# IQRB-1_Evo_board.net
KiCad netlist of a schematic drawn in EAGLE
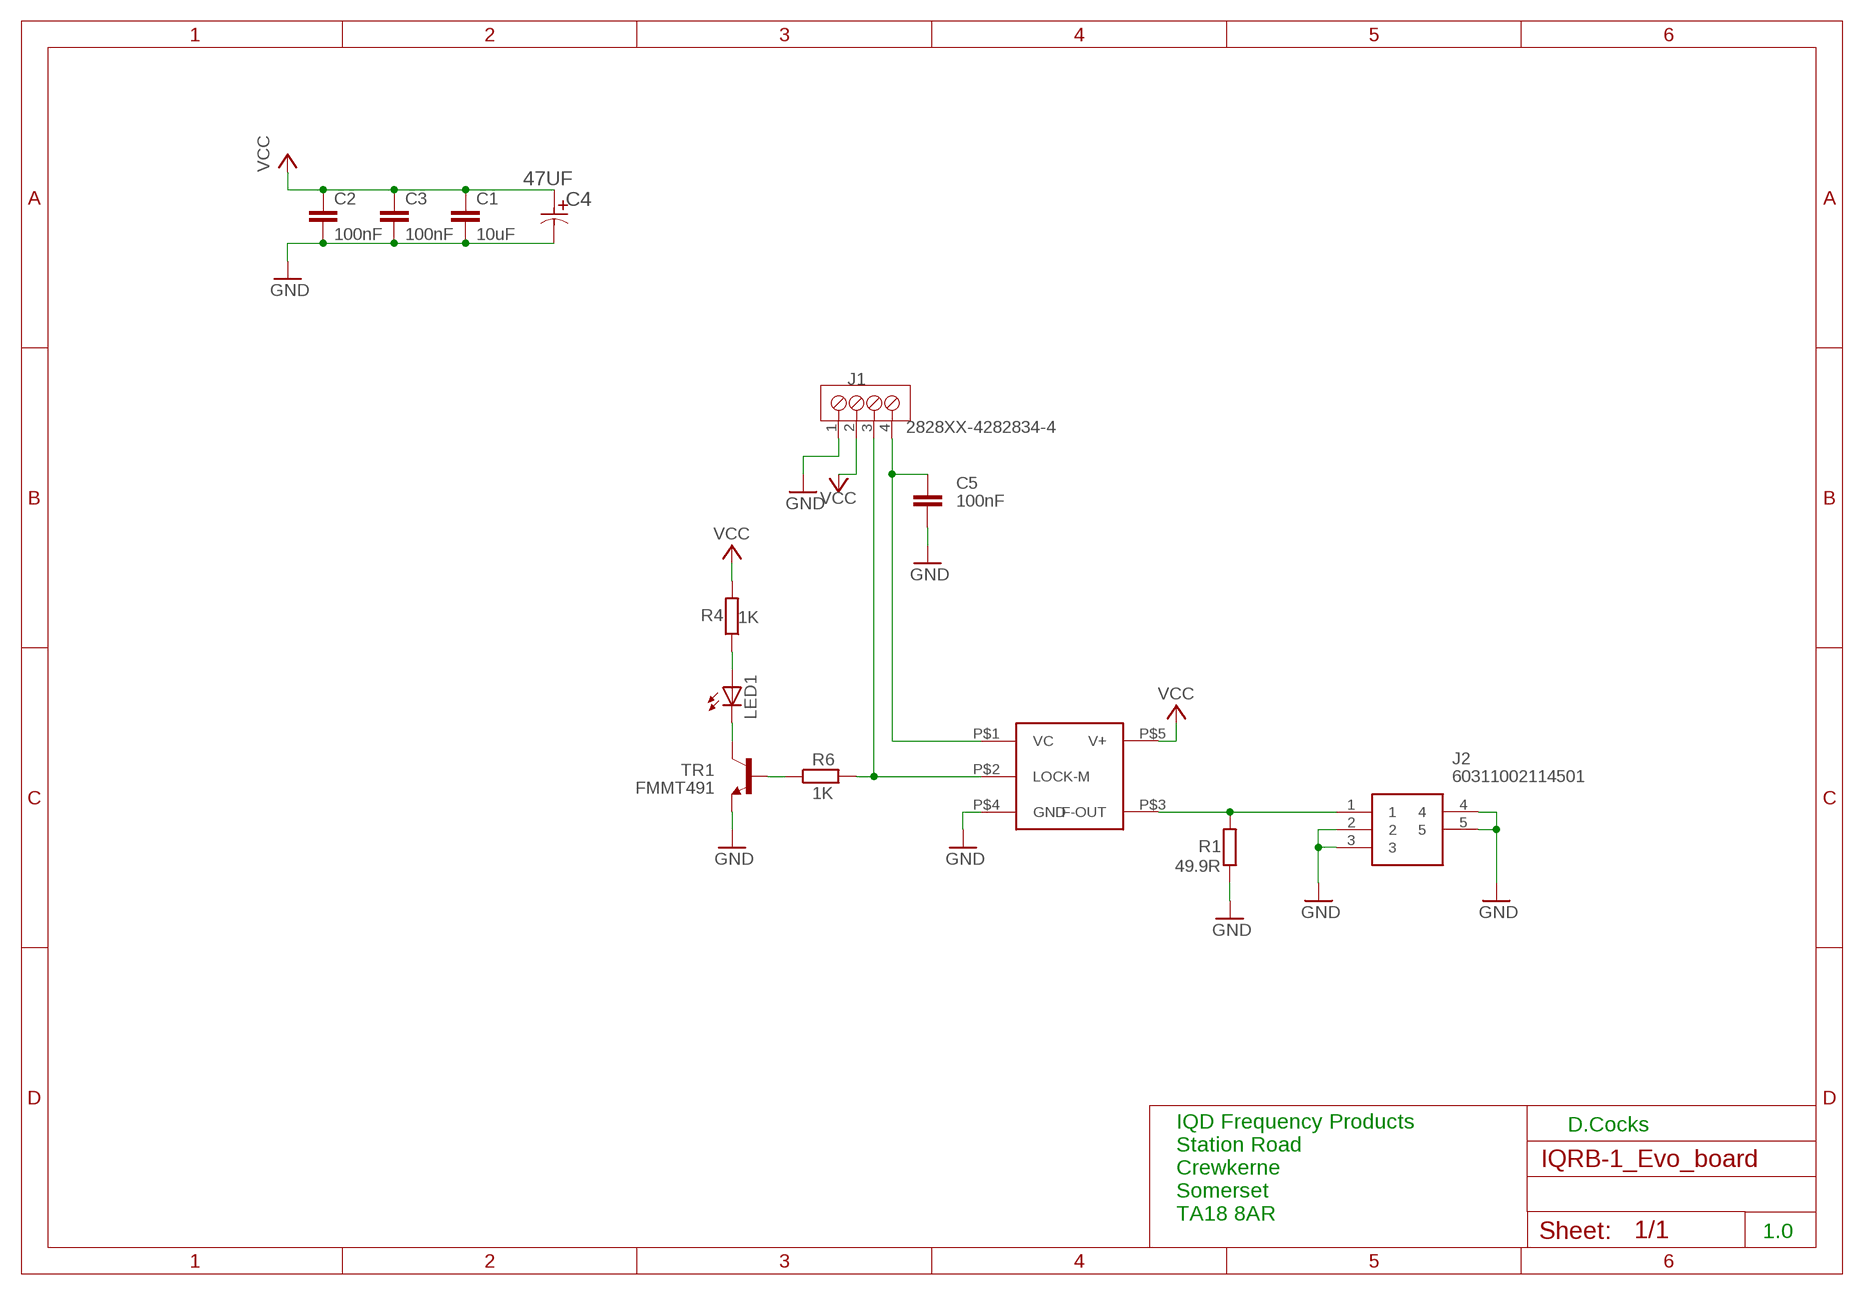
[diagram p0: schematic, sheet 1]

(export (version "E")
  (design (tool "Eeschema 10.0.6"))
  (components
    (comp (ref "C1")
      (value "10uF")
      (footprint "eagle-import:C0805")
      (libsource (lib "eagle-import") (part "C-EUC0805"))
    )
    (comp (ref "C2")
      (value "100nF")
      (footprint "eagle-import:C0805")
      (libsource (lib "eagle-import") (part "C-EUC0805"))
    )
    (comp (ref "C3")
      (value "100nF")
      (footprint "eagle-import:C0805")
      (libsource (lib "eagle-import") (part "C-EUC0805"))
    )
    (comp (ref "C4")
      (value "47UF")
      (footprint "eagle-import:CAPAE530X610N")
      (fields (field (name "MPN") "EEE-FK0J101UR") (field (name "TOLERANCE") "±20 %"))
      (libsource (lib "eagle-import") (part "EEE--CASE-CFK0J101UR"))
    )
    (comp (ref "C5")
      (value "100nF")
      (footprint "eagle-import:C0805")
      (libsource (lib "eagle-import") (part "C-EUC0805"))
    )
    (comp (ref "J1")
      (value "2828XX-4282834-4")
      (footprint "eagle-import:TERMBLK_254-4N")
      (fields (field (name "MANUFACTURER") "TE Connectivity AMP Connectors") (field (name "MPN") "282834-4"))
      (libsource (lib "eagle-import") (part "2828XX-4282834-4"))
    )
    (comp (ref "J2")
      (value "60311002114501")
      (footprint "eagle-import:60312002114503")
      (fields
        (field (name "MANUFACTURER_PART_NUMBER") "60312002114503")
        (field (name "MOUSER_PART_NUMBER") "710-60312002114503")
      )
      (libsource (lib "eagle-import") (part "60312002114503"))
    )
    (comp (ref "LED1")
      (value "LEDCHIP-LED0805")
      (footprint "eagle-import:CHIP-LED0805")
      (libsource (lib "eagle-import") (part "LEDCHIP-LED0805"))
    )
    (comp (ref "R1")
      (value "49.9R")
      (footprint "eagle-import:M1206")
      (libsource (lib "eagle-import") (part "resistor_348_R-EU_M1206"))
    )
    (comp (ref "R4")
      (value "1K")
      (footprint "eagle-import:M0805")
      (libsource (lib "eagle-import") (part "R-EU_M0805"))
    )
    (comp (ref "R6")
      (value "1K")
      (footprint "eagle-import:M0805")
      (libsource (lib "eagle-import") (part "R-EU_M0805"))
    )
    (comp (ref "TR1")
      (value "FMMT491")
      (footprint "eagle-import:SOT23-BEC")
      (libsource (lib "eagle-import") (part "BC817SMD-16LT1"))
    )
    (comp (ref "U$1")
      (value "RB1-DEVRUBID")
      (footprint "eagle-import:RB1-PACK")
      (libsource (lib "eagle-import") (part "RB1-DEVRUBID"))
    )
  )
  (nets
    (net (code "1") (name "GND") (class "Default")
      (node (ref "C1") (pin "2") (pinfunction "2_2") (pintype "passive"))
      (node (ref "C2") (pin "2") (pinfunction "2_2") (pintype "passive"))
      (node (ref "C3") (pin "2") (pinfunction "2_2") (pintype "passive"))
      (node (ref "C4") (pin "2") (pinfunction "2_2") (pintype "passive"))
      (node (ref "C5") (pin "2") (pinfunction "2_2") (pintype "passive"))
      (node (ref "J1") (pin "1") (pinfunction "1_1") (pintype "bidirectional"))
      (node (ref "J2") (pin "2") (pinfunction "2_2") (pintype "bidirectional"))
      (node (ref "J2") (pin "3") (pinfunction "3_3") (pintype "bidirectional"))
      (node (ref "J2") (pin "4") (pinfunction "4_4") (pintype "bidirectional"))
      (node (ref "J2") (pin "5") (pinfunction "5_5") (pintype "bidirectional"))
      (node (ref "R1") (pin "1") (pinfunction "1_1") (pintype "passive"))
      (node (ref "TR1") (pin "E") (pinfunction "E_E") (pintype "passive"))
      (node (ref "U$1") (pin "P$4") (pinfunction "GND_P$4") (pintype "bidirectional"))
    )
    (net (code "2") (name "Net-(LED1-PadA)") (class "Default")
      (node (ref "LED1") (pin "A") (pinfunction "A_A") (pintype "passive"))
      (node (ref "R4") (pin "1") (pinfunction "1_1") (pintype "passive"))
    )
    (net (code "3") (name "Net-(LED1-PadC)") (class "Default")
      (node (ref "LED1") (pin "C") (pinfunction "C_C") (pintype "passive"))
      (node (ref "TR1") (pin "C") (pinfunction "C_C") (pintype "passive"))
    )
    (net (code "4") (name "Net-(R6-Pad1)") (class "Default")
      (node (ref "R6") (pin "1") (pinfunction "1_1") (pintype "passive"))
      (node (ref "TR1") (pin "B") (pinfunction "B_B") (pintype "passive"))
    )
    (net (code "5") (name "Net-(U$1-F-OUT)") (class "Default")
      (node (ref "J2") (pin "1") (pinfunction "1_1") (pintype "bidirectional"))
      (node (ref "R1") (pin "2") (pinfunction "2_2") (pintype "passive"))
      (node (ref "U$1") (pin "P$3") (pinfunction "F-OUT_P$3") (pintype "bidirectional"))
    )
    (net (code "6") (name "Net-(U$1-LOCK-M)") (class "Default")
      (node (ref "J1") (pin "3") (pinfunction "3_3") (pintype "bidirectional"))
      (node (ref "R6") (pin "2") (pinfunction "2_2") (pintype "passive"))
      (node (ref "U$1") (pin "P$2") (pinfunction "LOCK-M_P$2") (pintype "bidirectional"))
    )
    (net (code "7") (name "Net-(U$1-VC)") (class "Default")
      (node (ref "C5") (pin "1") (pinfunction "1_1") (pintype "passive"))
      (node (ref "J1") (pin "4") (pinfunction "4_4") (pintype "bidirectional"))
      (node (ref "U$1") (pin "P$1") (pinfunction "VC_P$1") (pintype "bidirectional"))
    )
    (net (code "8") (name "VCC") (class "Default")
      (node (ref "C1") (pin "1") (pinfunction "1_1") (pintype "passive"))
      (node (ref "C2") (pin "1") (pinfunction "1_1") (pintype "passive"))
      (node (ref "C3") (pin "1") (pinfunction "1_1") (pintype "passive"))
      (node (ref "C4") (pin "1") (pinfunction "1_1") (pintype "passive"))
      (node (ref "J1") (pin "2") (pinfunction "2_2") (pintype "bidirectional"))
      (node (ref "R4") (pin "2") (pinfunction "2_2") (pintype "passive"))
      (node (ref "U$1") (pin "P$5") (pinfunction "V+_P$5") (pintype "bidirectional"))
    )
  )
)
